# SCH_LED_Driver_Battery-PWR.net
KiCad netlist of a schematic drawn in Altium Designer
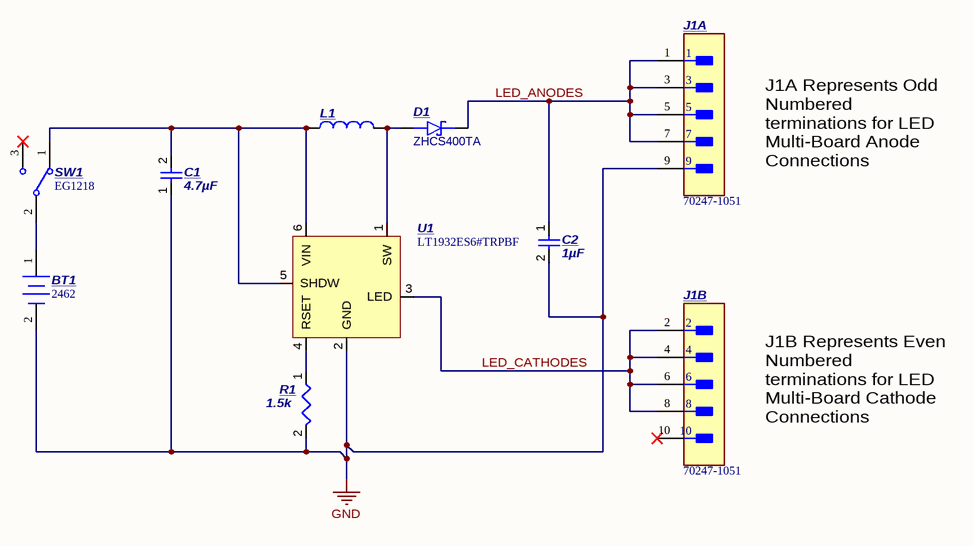
[diagram p0:  SCH_LED_Driver_Battery-PWR.SchDoc]

(export (version "E")
  (design (tool "Eeschema 10.0.6"))
  (components
    (comp (ref "BT1")
      (value "2462")
      (footprint "2462-Footprint-1")
      (description "Batteries/Accessories")
      (libsource (lib "Altium Designer Advanced Training Course 2 - A365") (part "Battery"))
    )
    (comp (ref "C1")
      (value "4.7µF")
      (footprint "0805_L")
      (fields (field (name "Comment") "JMK212BJ475KD-T"))
      (libsource (lib "Altium Designer Advanced Training Course 2 - A365") (part "CAP-NP-2"))
    )
    (comp (ref "C2")
      (value "1µF")
      (footprint "CAPC2013X135X45NL10T25")
      (description "Chip Capacitor, 1 uF, +/- 10%, 50 V, 0805 (2012 Metric)")
      (fields (field (name "TOLERANCE") "10%") (field (name "Comment") "Capacitor 1 uF +/- 10% 50 V 0805"))
      (libsource (lib "Altium Designer Advanced Training Course 2 - A365") (part "CAP-NP-2"))
    )
    (comp (ref "D1")
      (value "ZHCS400TA")
      (footprint "FP-SOD323-IPC_C")
      (description "Rectifier Diode, Schottky, 1 Phase, 1 Element, 0.4A, 40V V(RRM), Silicon")
      (libsource (lib "Altium Designer Advanced Training Course 2 - A365") (part "DIODE-SKY-2"))
    )
    (comp (ref "J1")
      (value "70247-1051")
      (footprint "FP-70247-1051-MFG")
      (libsource (lib "Altium Designer Advanced Training Course 2 - A365") (part "b90c43bfdb997d6037ddb7f87098795"))
    )
    (comp (ref "L1")
      (value "744032004")
      (footprint "WE-LQ_1210")
      (description "General Purpose Inductor, 4.7uH, 20%, 1 Element, Ferrite-Core, SMD, 1210")
      (fields (field (name "TOLERANCE") "20%"))
      (libsource (lib "Altium Designer Advanced Training Course 2 - A365") (part "IND-2"))
    )
    (comp (ref "R1")
      (value "1.5k")
      (footprint "RESC2013X60X35LL10T20")
      (fields
        (field (name "POWER") "125mW")
        (field (name "TOLERANCE") "1%")
        (field (name "Comment") "RC0805FR-071K5L")
      )
      (libsource (lib "Altium Designer Advanced Training Course 2 - A365") (part "RES-2"))
    )
    (comp (ref "SW1")
      (value "EG1218")
      (footprint "ESWI-EG1218_V")
      (description "Slide Switch, SPDT, 500 V, -20 to 70 degC, 3-Pin THD, RoHS, Bulk")
      (fields (field (name "MANUFACTURER") "E-Switch"))
      (libsource (lib "Altium Designer Advanced Training Course 2 - A365") (part "SW-SPDT-3_B"))
    )
    (comp (ref "U1")
      (value "LT1932ES6#TRPBF")
      (footprint "DDC0006A_N")
      (description "Switching Regulator, Current-mode, 0.78A, 1600kHz Switching Freq-Max, PDSO6")
      (libsource (lib "Altium Designer Advanced Training Course 2 - A365") (part "LT1932ES6#TRPBF-Symbol-1"))
    )
  )
  (nets
    (net (code "1") (name "/LED_ANODES") (class "Default")
      (node (ref "C2") (pin "1") (pinfunction "1_1") (pintype "passive"))
      (node (ref "D1") (pin "1") (pinfunction "K_1") (pintype "passive"))
      (node (ref "J1") (pin "1") (pinfunction "1_1") (pintype "passive"))
      (node (ref "J1") (pin "3") (pinfunction "3_3") (pintype "passive"))
      (node (ref "J1") (pin "5") (pinfunction "5_5") (pintype "passive"))
      (node (ref "J1") (pin "7") (pinfunction "7_7") (pintype "passive"))
    )
    (net (code "2") (name "/LED_CATHODES") (class "Default")
      (node (ref "J1") (pin "2") (pinfunction "2_2") (pintype "passive"))
      (node (ref "J1") (pin "4") (pinfunction "4_4") (pintype "passive"))
      (node (ref "J1") (pin "6") (pinfunction "6_6") (pintype "passive"))
      (node (ref "J1") (pin "8") (pinfunction "8_8") (pintype "passive"))
      (node (ref "U1") (pin "3") (pinfunction "LED_3") (pintype "passive"))
    )
    (net (code "3") (name "GND") (class "Default")
      (node (ref "BT1") (pin "2") (pinfunction "-_2") (pintype "passive"))
      (node (ref "C1") (pin "1") (pinfunction "1_1") (pintype "passive"))
      (node (ref "C2") (pin "2") (pinfunction "2_2") (pintype "passive"))
      (node (ref "J1") (pin "9") (pinfunction "9_9") (pintype "passive"))
      (node (ref "R1") (pin "2") (pinfunction "2_2") (pintype "passive"))
      (node (ref "U1") (pin "2") (pinfunction "GND_2") (pintype "passive"))
    )
    (net (code "4") (name "Net-(BT1-+)") (class "Default")
      (node (ref "BT1") (pin "1") (pinfunction "+_1") (pintype "passive"))
      (node (ref "SW1") (pin "2") (pinfunction "COM_2") (pintype "passive"))
    )
    (net (code "5") (name "Net-(D1-A)") (class "Default")
      (node (ref "D1") (pin "2") (pinfunction "A_2") (pintype "passive"))
      (node (ref "L1") (pin "2") (pinfunction "2_2") (pintype "passive"))
      (node (ref "U1") (pin "1") (pinfunction "SW_1") (pintype "passive"))
    )
    (net (code "6") (name "Net-(U1-RSET)") (class "Default")
      (node (ref "R1") (pin "1") (pinfunction "1_1") (pintype "passive"))
      (node (ref "U1") (pin "4") (pinfunction "RSET_4") (pintype "passive"))
    )
    (net (code "7") (name "Net-(U1-SHDW)") (class "Default")
      (node (ref "C1") (pin "2") (pinfunction "2_2") (pintype "passive"))
      (node (ref "L1") (pin "1") (pinfunction "1_1") (pintype "passive"))
      (node (ref "SW1") (pin "1") (pinfunction "1_1") (pintype "passive"))
      (node (ref "U1") (pin "5") (pinfunction "SHDW_5") (pintype "passive"))
      (node (ref "U1") (pin "6") (pinfunction "VIN_6") (pintype "passive"))
    )
    (net (code "8") (name "unconnected-(J1-Pad10)") (class "Default")
      (node (ref "J1") (pin "10") (pinfunction "10_10") (pintype "passive+no_connect"))
    )
    (net (code "9") (name "unconnected-(SW1-Pad3)") (class "Default")
      (node (ref "SW1") (pin "3") (pinfunction "3_3") (pintype "passive+no_connect"))
    )
  )
)
